# 12vto15v_mosfet_control.net
KiCad netlist of a schematic drawn in Altium Designer
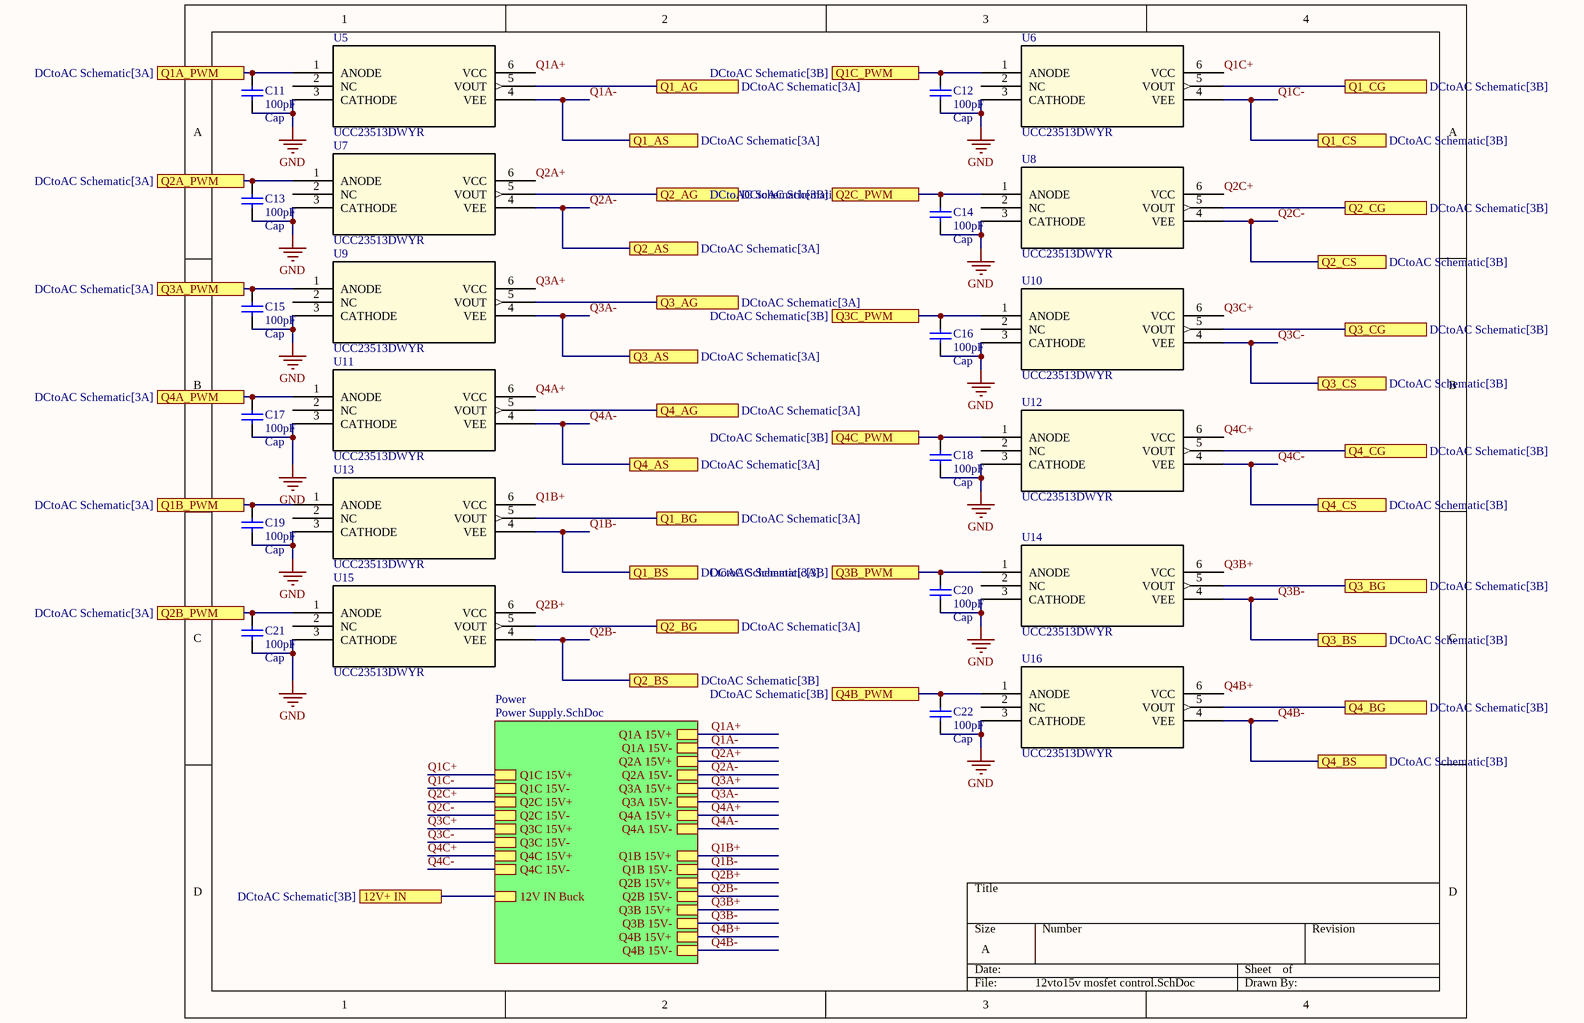
[diagram p0: 12vto15v mosfet control.SchDoc]

(export (version "E")
  (design (tool "Eeschema 10.0.6"))
  (components
    (comp (ref "C11")
      (value "Cap")
      (footprint "RAD-0.3")
      (description "Capacitor")
      (fields (field (name "ALTIUM_VALUE") "100pF") (field (name "PUBLISHER") "Altium Limited"))
      (libsource (lib "Miscellaneous Devices") (part "Cap"))
    )
    (comp (ref "C12")
      (value "Cap")
      (footprint "RAD-0.3")
      (description "Capacitor")
      (fields (field (name "ALTIUM_VALUE") "100pF") (field (name "PUBLISHER") "Altium Limited"))
      (libsource (lib "Miscellaneous Devices") (part "Cap"))
    )
    (comp (ref "C13")
      (value "Cap")
      (footprint "RAD-0.3")
      (description "Capacitor")
      (fields (field (name "ALTIUM_VALUE") "100pF") (field (name "PUBLISHER") "Altium Limited"))
      (libsource (lib "Miscellaneous Devices") (part "Cap"))
    )
    (comp (ref "C14")
      (value "Cap")
      (footprint "RAD-0.3")
      (description "Capacitor")
      (fields (field (name "ALTIUM_VALUE") "100pF") (field (name "PUBLISHER") "Altium Limited"))
      (libsource (lib "Miscellaneous Devices") (part "Cap"))
    )
    (comp (ref "C15")
      (value "Cap")
      (footprint "RAD-0.3")
      (description "Capacitor")
      (fields (field (name "ALTIUM_VALUE") "100pF") (field (name "PUBLISHER") "Altium Limited"))
      (libsource (lib "Miscellaneous Devices") (part "Cap"))
    )
    (comp (ref "C16")
      (value "Cap")
      (footprint "RAD-0.3")
      (description "Capacitor")
      (fields (field (name "ALTIUM_VALUE") "100pF") (field (name "PUBLISHER") "Altium Limited"))
      (libsource (lib "Miscellaneous Devices") (part "Cap"))
    )
    (comp (ref "C17")
      (value "Cap")
      (footprint "RAD-0.3")
      (description "Capacitor")
      (fields (field (name "ALTIUM_VALUE") "100pF") (field (name "PUBLISHER") "Altium Limited"))
      (libsource (lib "Miscellaneous Devices") (part "Cap"))
    )
    (comp (ref "C18")
      (value "Cap")
      (footprint "RAD-0.3")
      (description "Capacitor")
      (fields (field (name "ALTIUM_VALUE") "100pF") (field (name "PUBLISHER") "Altium Limited"))
      (libsource (lib "Miscellaneous Devices") (part "Cap"))
    )
    (comp (ref "C19")
      (value "Cap")
      (footprint "RAD-0.3")
      (description "Capacitor")
      (fields (field (name "ALTIUM_VALUE") "100pF") (field (name "PUBLISHER") "Altium Limited"))
      (libsource (lib "Miscellaneous Devices") (part "Cap"))
    )
    (comp (ref "C20")
      (value "Cap")
      (footprint "RAD-0.3")
      (description "Capacitor")
      (fields (field (name "ALTIUM_VALUE") "100pF") (field (name "PUBLISHER") "Altium Limited"))
      (libsource (lib "Miscellaneous Devices") (part "Cap"))
    )
    (comp (ref "C21")
      (value "Cap")
      (footprint "RAD-0.3")
      (description "Capacitor")
      (fields (field (name "ALTIUM_VALUE") "100pF") (field (name "PUBLISHER") "Altium Limited"))
      (libsource (lib "Miscellaneous Devices") (part "Cap"))
    )
    (comp (ref "C22")
      (value "Cap")
      (footprint "RAD-0.3")
      (description "Capacitor")
      (fields (field (name "ALTIUM_VALUE") "100pF") (field (name "PUBLISHER") "Altium Limited"))
      (libsource (lib "Miscellaneous Devices") (part "Cap"))
    )
    (comp (ref "U5")
      (value "UCC23513DWYR")
      (footprint "Senior Design PCB Library:DWY6_TEX")
      (description "No Description Available")
      (libsource (lib "Senior Design Schematic Library") (part "UCC23513DWYR"))
    )
    (comp (ref "U6")
      (value "UCC23513DWYR")
      (footprint "Senior Design PCB Library:DWY6_TEX")
      (description "No Description Available")
      (libsource (lib "Senior Design Schematic Library") (part "UCC23513DWYR"))
    )
    (comp (ref "U7")
      (value "UCC23513DWYR")
      (footprint "Senior Design PCB Library:DWY6_TEX")
      (description "No Description Available")
      (libsource (lib "Senior Design Schematic Library") (part "UCC23513DWYR"))
    )
    (comp (ref "U8")
      (value "UCC23513DWYR")
      (footprint "Senior Design PCB Library:DWY6_TEX")
      (description "No Description Available")
      (libsource (lib "Senior Design Schematic Library") (part "UCC23513DWYR"))
    )
    (comp (ref "U9")
      (value "UCC23513DWYR")
      (footprint "Senior Design PCB Library:DWY6_TEX")
      (description "No Description Available")
      (libsource (lib "Senior Design Schematic Library") (part "UCC23513DWYR"))
    )
    (comp (ref "U10")
      (value "UCC23513DWYR")
      (footprint "Senior Design PCB Library:DWY6_TEX")
      (description "No Description Available")
      (libsource (lib "Senior Design Schematic Library") (part "UCC23513DWYR"))
    )
    (comp (ref "U11")
      (value "UCC23513DWYR")
      (footprint "Senior Design PCB Library:DWY6_TEX")
      (description "No Description Available")
      (libsource (lib "Senior Design Schematic Library") (part "UCC23513DWYR"))
    )
    (comp (ref "U12")
      (value "UCC23513DWYR")
      (footprint "Senior Design PCB Library:DWY6_TEX")
      (description "No Description Available")
      (libsource (lib "Senior Design Schematic Library") (part "UCC23513DWYR"))
    )
    (comp (ref "U13")
      (value "UCC23513DWYR")
      (footprint "Senior Design PCB Library:DWY6_TEX")
      (description "No Description Available")
      (libsource (lib "Senior Design Schematic Library") (part "UCC23513DWYR"))
    )
    (comp (ref "U14")
      (value "UCC23513DWYR")
      (footprint "Senior Design PCB Library:DWY6_TEX")
      (description "No Description Available")
      (libsource (lib "Senior Design Schematic Library") (part "UCC23513DWYR"))
    )
    (comp (ref "U15")
      (value "UCC23513DWYR")
      (footprint "Senior Design PCB Library:DWY6_TEX")
      (description "No Description Available")
      (libsource (lib "Senior Design Schematic Library") (part "UCC23513DWYR"))
    )
    (comp (ref "U16")
      (value "UCC23513DWYR")
      (footprint "Senior Design PCB Library:DWY6_TEX")
      (description "No Description Available")
      (libsource (lib "Senior Design Schematic Library") (part "UCC23513DWYR"))
    )
  )
  (nets
    (net (code "2") (name "/Q1A+") (class "Default")
      (node (ref "U5") (pin "6") (pinfunction "VCC_6") (pintype "power_in"))
    )
    (net (code "3") (name "/Q1A-") (class "Default")
      (node (ref "U5") (pin "4") (pinfunction "VEE_4") (pintype "power_in"))
    )
    (net (code "4") (name "/Q1A_PWM") (class "Default")
      (node (ref "C11") (pin "2") (pinfunction "2_2") (pintype "passive"))
      (node (ref "U5") (pin "1") (pinfunction "ANODE_1") (pintype "passive"))
    )
    (net (code "5") (name "/Q1B+") (class "Default")
      (node (ref "U13") (pin "6") (pinfunction "VCC_6") (pintype "power_in"))
    )
    (net (code "6") (name "/Q1B-") (class "Default")
      (node (ref "U13") (pin "4") (pinfunction "VEE_4") (pintype "power_in"))
    )
    (net (code "7") (name "/Q1B_PWM") (class "Default")
      (node (ref "C19") (pin "2") (pinfunction "2_2") (pintype "passive"))
      (node (ref "U13") (pin "1") (pinfunction "ANODE_1") (pintype "passive"))
    )
    (net (code "8") (name "/Q1C+") (class "Default")
      (node (ref "U6") (pin "6") (pinfunction "VCC_6") (pintype "power_in"))
    )
    (net (code "9") (name "/Q1C-") (class "Default")
      (node (ref "U6") (pin "4") (pinfunction "VEE_4") (pintype "power_in"))
    )
    (net (code "10") (name "/Q1C_PWM") (class "Default")
      (node (ref "C12") (pin "2") (pinfunction "2_2") (pintype "passive"))
      (node (ref "U6") (pin "1") (pinfunction "ANODE_1") (pintype "passive"))
    )
    (net (code "11") (name "/Q1_AG") (class "Default")
      (node (ref "U5") (pin "5") (pinfunction "VOUT_5") (pintype "output"))
    )
    (net (code "12") (name "/Q1_BG") (class "Default")
      (node (ref "U13") (pin "5") (pinfunction "VOUT_5") (pintype "output"))
    )
    (net (code "13") (name "/Q1_CG") (class "Default")
      (node (ref "U6") (pin "5") (pinfunction "VOUT_5") (pintype "output"))
    )
    (net (code "14") (name "/Q2A+") (class "Default")
      (node (ref "U7") (pin "6") (pinfunction "VCC_6") (pintype "power_in"))
    )
    (net (code "15") (name "/Q2A-") (class "Default")
      (node (ref "U7") (pin "4") (pinfunction "VEE_4") (pintype "power_in"))
    )
    (net (code "16") (name "/Q2A_PWM") (class "Default")
      (node (ref "C13") (pin "2") (pinfunction "2_2") (pintype "passive"))
      (node (ref "U7") (pin "1") (pinfunction "ANODE_1") (pintype "passive"))
    )
    (net (code "17") (name "/Q2B+") (class "Default")
      (node (ref "U15") (pin "6") (pinfunction "VCC_6") (pintype "power_in"))
    )
    (net (code "18") (name "/Q2B-") (class "Default")
      (node (ref "U15") (pin "4") (pinfunction "VEE_4") (pintype "power_in"))
    )
    (net (code "19") (name "/Q2B_PWM") (class "Default")
      (node (ref "C21") (pin "2") (pinfunction "2_2") (pintype "passive"))
      (node (ref "U15") (pin "1") (pinfunction "ANODE_1") (pintype "passive"))
    )
    (net (code "20") (name "/Q2C+") (class "Default")
      (node (ref "U8") (pin "6") (pinfunction "VCC_6") (pintype "power_in"))
    )
    (net (code "21") (name "/Q2C-") (class "Default")
      (node (ref "U8") (pin "4") (pinfunction "VEE_4") (pintype "power_in"))
    )
    (net (code "22") (name "/Q2C_PWM") (class "Default")
      (node (ref "C14") (pin "2") (pinfunction "2_2") (pintype "passive"))
      (node (ref "U8") (pin "1") (pinfunction "ANODE_1") (pintype "passive"))
    )
    (net (code "23") (name "/Q2_AG") (class "Default")
      (node (ref "U7") (pin "5") (pinfunction "VOUT_5") (pintype "output"))
    )
    (net (code "24") (name "/Q2_BG") (class "Default")
      (node (ref "U15") (pin "5") (pinfunction "VOUT_5") (pintype "output"))
    )
    (net (code "25") (name "/Q2_CG") (class "Default")
      (node (ref "U8") (pin "5") (pinfunction "VOUT_5") (pintype "output"))
    )
    (net (code "26") (name "/Q3A+") (class "Default")
      (node (ref "U9") (pin "6") (pinfunction "VCC_6") (pintype "power_in"))
    )
    (net (code "27") (name "/Q3A-") (class "Default")
      (node (ref "U9") (pin "4") (pinfunction "VEE_4") (pintype "power_in"))
    )
    (net (code "28") (name "/Q3A_PWM") (class "Default")
      (node (ref "C15") (pin "2") (pinfunction "2_2") (pintype "passive"))
      (node (ref "U9") (pin "1") (pinfunction "ANODE_1") (pintype "passive"))
    )
    (net (code "29") (name "/Q3B+") (class "Default")
      (node (ref "U14") (pin "6") (pinfunction "VCC_6") (pintype "power_in"))
    )
    (net (code "30") (name "/Q3B-") (class "Default")
      (node (ref "U14") (pin "4") (pinfunction "VEE_4") (pintype "power_in"))
    )
    (net (code "31") (name "/Q3B_PWM") (class "Default")
      (node (ref "C20") (pin "2") (pinfunction "2_2") (pintype "passive"))
      (node (ref "U14") (pin "1") (pinfunction "ANODE_1") (pintype "passive"))
    )
    (net (code "32") (name "/Q3C+") (class "Default")
      (node (ref "U10") (pin "6") (pinfunction "VCC_6") (pintype "power_in"))
    )
    (net (code "33") (name "/Q3C-") (class "Default")
      (node (ref "U10") (pin "4") (pinfunction "VEE_4") (pintype "power_in"))
    )
    (net (code "34") (name "/Q3C_PWM") (class "Default")
      (node (ref "C16") (pin "2") (pinfunction "2_2") (pintype "passive"))
      (node (ref "U10") (pin "1") (pinfunction "ANODE_1") (pintype "passive"))
    )
    (net (code "35") (name "/Q3_AG") (class "Default")
      (node (ref "U9") (pin "5") (pinfunction "VOUT_5") (pintype "output"))
    )
    (net (code "36") (name "/Q3_BG") (class "Default")
      (node (ref "U14") (pin "5") (pinfunction "VOUT_5") (pintype "output"))
    )
    (net (code "37") (name "/Q3_CG") (class "Default")
      (node (ref "U10") (pin "5") (pinfunction "VOUT_5") (pintype "output"))
    )
    (net (code "38") (name "/Q4A+") (class "Default")
      (node (ref "U11") (pin "6") (pinfunction "VCC_6") (pintype "power_in"))
    )
    (net (code "39") (name "/Q4A-") (class "Default")
      (node (ref "U11") (pin "4") (pinfunction "VEE_4") (pintype "power_in"))
    )
    (net (code "40") (name "/Q4A_PWM") (class "Default")
      (node (ref "C17") (pin "2") (pinfunction "2_2") (pintype "passive"))
      (node (ref "U11") (pin "1") (pinfunction "ANODE_1") (pintype "passive"))
    )
    (net (code "41") (name "/Q4B+") (class "Default")
      (node (ref "U16") (pin "6") (pinfunction "VCC_6") (pintype "power_in"))
    )
    (net (code "42") (name "/Q4B-") (class "Default")
      (node (ref "U16") (pin "4") (pinfunction "VEE_4") (pintype "power_in"))
    )
    (net (code "43") (name "/Q4B_PWM") (class "Default")
      (node (ref "C22") (pin "2") (pinfunction "2_2") (pintype "passive"))
      (node (ref "U16") (pin "1") (pinfunction "ANODE_1") (pintype "passive"))
    )
    (net (code "44") (name "/Q4C+") (class "Default")
      (node (ref "U12") (pin "6") (pinfunction "VCC_6") (pintype "power_in"))
    )
    (net (code "45") (name "/Q4C-") (class "Default")
      (node (ref "U12") (pin "4") (pinfunction "VEE_4") (pintype "power_in"))
    )
    (net (code "46") (name "/Q4C_PWM") (class "Default")
      (node (ref "C18") (pin "2") (pinfunction "2_2") (pintype "passive"))
      (node (ref "U12") (pin "1") (pinfunction "ANODE_1") (pintype "passive"))
    )
    (net (code "47") (name "/Q4_AG") (class "Default")
      (node (ref "U11") (pin "5") (pinfunction "VOUT_5") (pintype "output"))
    )
    (net (code "48") (name "/Q4_BG") (class "Default")
      (node (ref "U16") (pin "5") (pinfunction "VOUT_5") (pintype "output"))
    )
    (net (code "49") (name "/Q4_CG") (class "Default")
      (node (ref "U12") (pin "5") (pinfunction "VOUT_5") (pintype "output"))
    )
    (net (code "50") (name "GND") (class "Default")
      (node (ref "C11") (pin "1") (pinfunction "1_1") (pintype "passive"))
      (node (ref "C12") (pin "1") (pinfunction "1_1") (pintype "passive"))
      (node (ref "C13") (pin "1") (pinfunction "1_1") (pintype "passive"))
      (node (ref "C14") (pin "1") (pinfunction "1_1") (pintype "passive"))
      (node (ref "C15") (pin "1") (pinfunction "1_1") (pintype "passive"))
      (node (ref "C16") (pin "1") (pinfunction "1_1") (pintype "passive"))
      (node (ref "C17") (pin "1") (pinfunction "1_1") (pintype "passive"))
      (node (ref "C18") (pin "1") (pinfunction "1_1") (pintype "passive"))
      (node (ref "C19") (pin "1") (pinfunction "1_1") (pintype "passive"))
      (node (ref "C20") (pin "1") (pinfunction "1_1") (pintype "passive"))
      (node (ref "C21") (pin "1") (pinfunction "1_1") (pintype "passive"))
      (node (ref "C22") (pin "1") (pinfunction "1_1") (pintype "passive"))
      (node (ref "U10") (pin "3") (pinfunction "CATHODE_3") (pintype "passive"))
      (node (ref "U11") (pin "3") (pinfunction "CATHODE_3") (pintype "passive"))
      (node (ref "U12") (pin "3") (pinfunction "CATHODE_3") (pintype "passive"))
      (node (ref "U13") (pin "3") (pinfunction "CATHODE_3") (pintype "passive"))
      (node (ref "U14") (pin "3") (pinfunction "CATHODE_3") (pintype "passive"))
      (node (ref "U15") (pin "3") (pinfunction "CATHODE_3") (pintype "passive"))
      (node (ref "U16") (pin "3") (pinfunction "CATHODE_3") (pintype "passive"))
      (node (ref "U5") (pin "3") (pinfunction "CATHODE_3") (pintype "passive"))
      (node (ref "U6") (pin "3") (pinfunction "CATHODE_3") (pintype "passive"))
      (node (ref "U7") (pin "3") (pinfunction "CATHODE_3") (pintype "passive"))
      (node (ref "U8") (pin "3") (pinfunction "CATHODE_3") (pintype "passive"))
      (node (ref "U9") (pin "3") (pinfunction "CATHODE_3") (pintype "passive"))
    )
    (net (code "51") (name "unconnected-(U5-NC-Pad2)") (class "Default")
      (node (ref "U5") (pin "2") (pinfunction "NC_2") (pintype "passive"))
    )
    (net (code "52") (name "unconnected-(U6-NC-Pad2)") (class "Default")
      (node (ref "U6") (pin "2") (pinfunction "NC_2") (pintype "passive"))
    )
    (net (code "53") (name "unconnected-(U7-NC-Pad2)") (class "Default")
      (node (ref "U7") (pin "2") (pinfunction "NC_2") (pintype "passive"))
    )
    (net (code "54") (name "unconnected-(U8-NC-Pad2)") (class "Default")
      (node (ref "U8") (pin "2") (pinfunction "NC_2") (pintype "passive"))
    )
    (net (code "55") (name "unconnected-(U9-NC-Pad2)") (class "Default")
      (node (ref "U9") (pin "2") (pinfunction "NC_2") (pintype "passive"))
    )
    (net (code "56") (name "unconnected-(U10-NC-Pad2)") (class "Default")
      (node (ref "U10") (pin "2") (pinfunction "NC_2") (pintype "passive"))
    )
    (net (code "57") (name "unconnected-(U11-NC-Pad2)") (class "Default")
      (node (ref "U11") (pin "2") (pinfunction "NC_2") (pintype "passive"))
    )
    (net (code "58") (name "unconnected-(U12-NC-Pad2)") (class "Default")
      (node (ref "U12") (pin "2") (pinfunction "NC_2") (pintype "passive"))
    )
    (net (code "59") (name "unconnected-(U13-NC-Pad2)") (class "Default")
      (node (ref "U13") (pin "2") (pinfunction "NC_2") (pintype "passive"))
    )
    (net (code "60") (name "unconnected-(U14-NC-Pad2)") (class "Default")
      (node (ref "U14") (pin "2") (pinfunction "NC_2") (pintype "passive"))
    )
    (net (code "61") (name "unconnected-(U15-NC-Pad2)") (class "Default")
      (node (ref "U15") (pin "2") (pinfunction "NC_2") (pintype "passive"))
    )
    (net (code "62") (name "unconnected-(U16-NC-Pad2)") (class "Default")
      (node (ref "U16") (pin "2") (pinfunction "NC_2") (pintype "passive"))
    )
  )
)
